# rapidshark-display-butt-mk-1_2.net
KiCad netlist of a schematic drawn in EAGLE
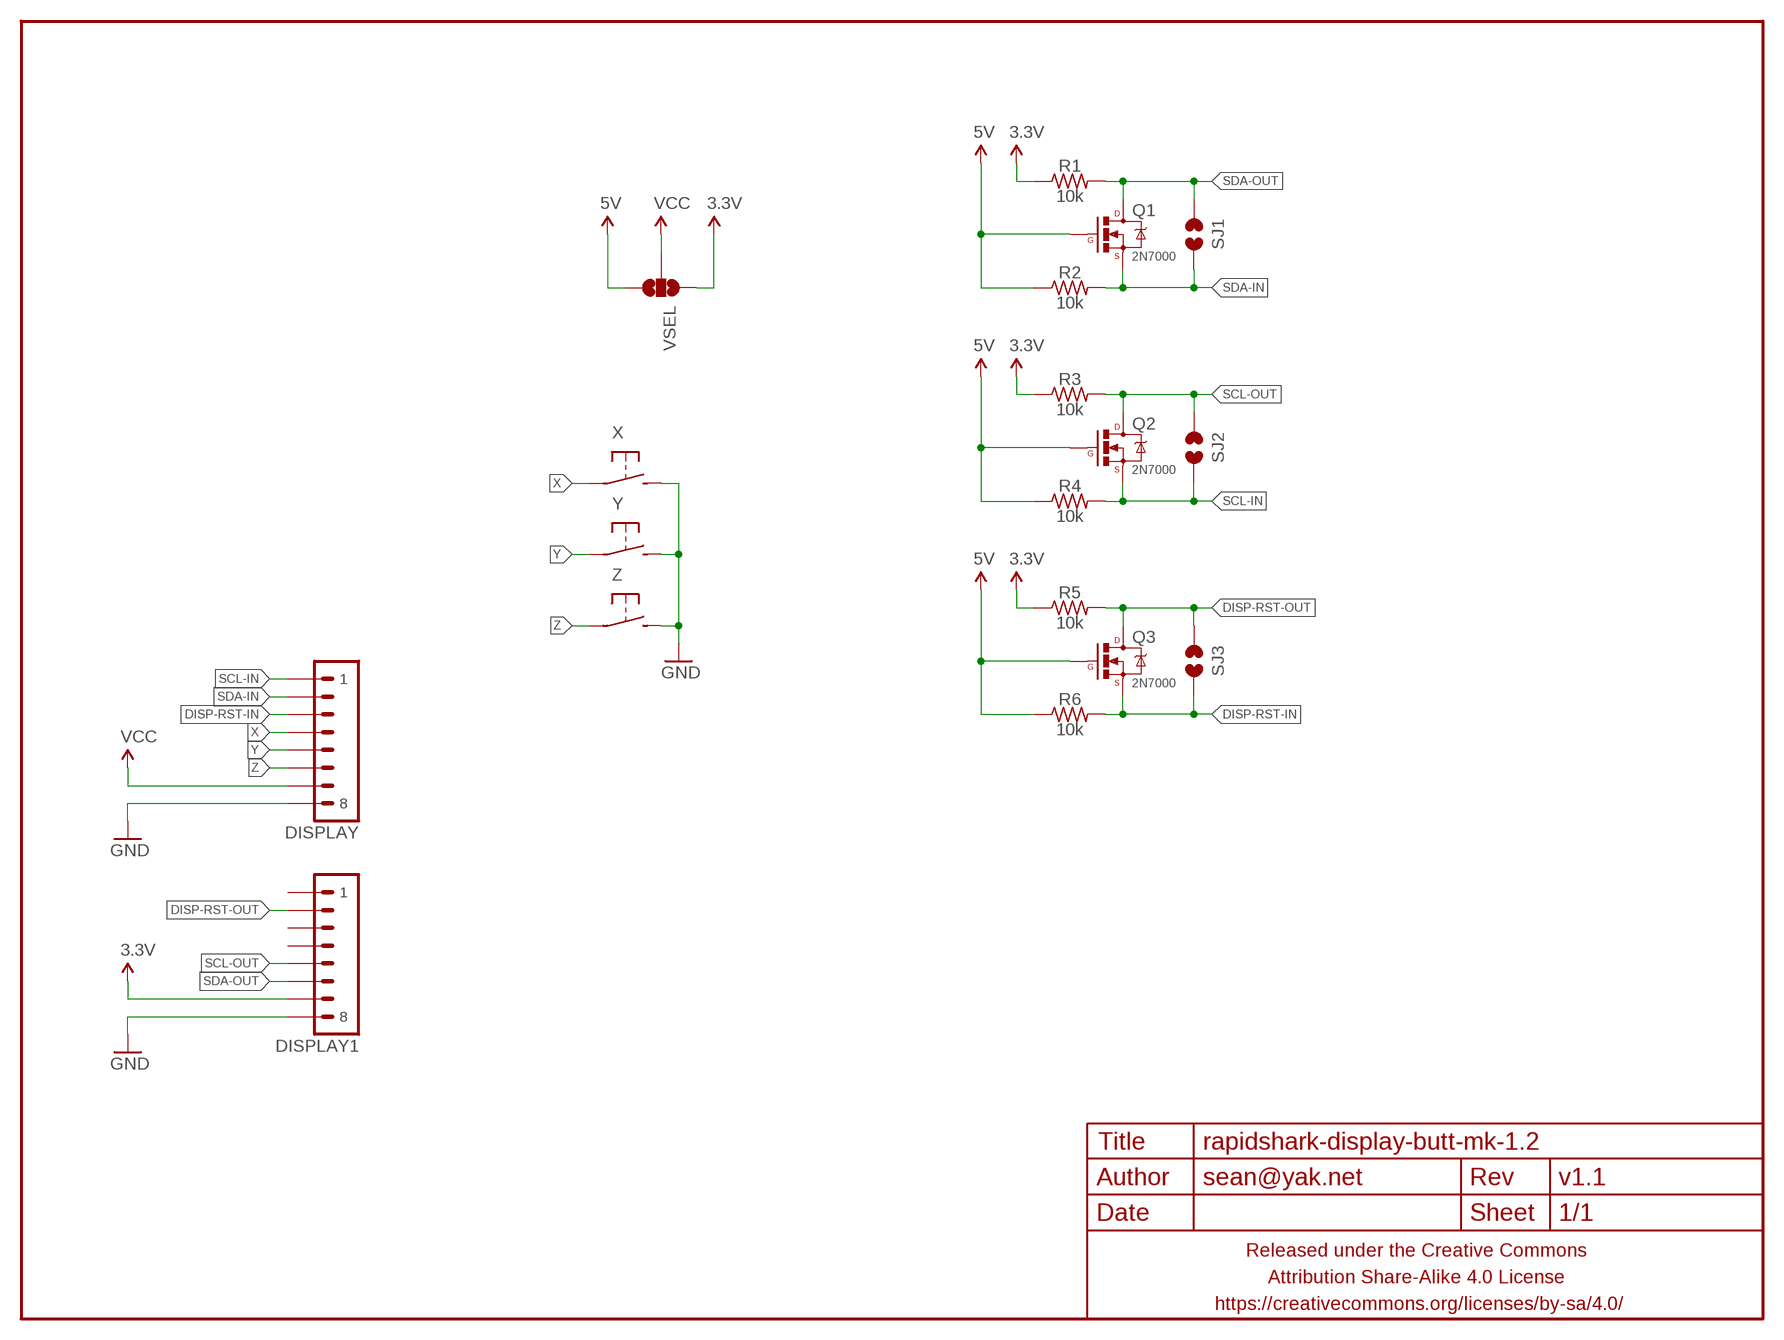
[diagram p0: schematic, sheet 1]

(export (version "E")
  (design (tool "Eeschema 10.0.6"))
  (components
    (comp (ref "DISPLAY")
      (value "M08JST-PH-VERT-PTH")
      (footprint "eagle-import:JST-8-VERT-PTH")
      (libsource (lib "eagle-import") (part "M08JST-PH-VERT-PTH"))
    )
    (comp (ref "DISPLAY1")
      (value "M081X08")
      (footprint "eagle-import:1X08")
      (libsource (lib "eagle-import") (part "M081X08"))
    )
    (comp (ref "FRAME1")
      (value "FRAME-LETTERNO_PACKAGE")
      (footprint "eagle-import:DUMMY")
      (fields (field (name "DESIGNER") "sean@yak.net") (field (name "VERSION") "v1.1"))
      (libsource (lib "eagle-import") (part "FRAME-LETTERNO_PACKAGE"))
    )
    (comp (ref "Q1")
      (value "2N7000")
      (footprint "eagle-import:TO-92-AMMO")
      (libsource (lib "eagle-import") (part "MOSFET-NCHANNEL2N7000-AMMO"))
    )
    (comp (ref "Q2")
      (value "2N7000")
      (footprint "eagle-import:TO-92-AMMO")
      (libsource (lib "eagle-import") (part "MOSFET-NCHANNEL2N7000-AMMO"))
    )
    (comp (ref "Q3")
      (value "2N7000")
      (footprint "eagle-import:TO-92-AMMO")
      (libsource (lib "eagle-import") (part "MOSFET-NCHANNEL2N7000-AMMO"))
    )
    (comp (ref "R1")
      (value "10k")
      (footprint "eagle-import:RESISTOR-AXIAL-PTH-5.08MM")
      (libsource (lib "eagle-import") (part "RESISTORPTH-AXIAL-5.08MM"))
    )
    (comp (ref "R2")
      (value "10k")
      (footprint "eagle-import:RESISTOR-AXIAL-PTH-5.08MM")
      (libsource (lib "eagle-import") (part "RESISTORPTH-AXIAL-5.08MM"))
    )
    (comp (ref "R3")
      (value "10k")
      (footprint "eagle-import:RESISTOR-AXIAL-PTH-5.08MM")
      (libsource (lib "eagle-import") (part "RESISTORPTH-AXIAL-5.08MM"))
    )
    (comp (ref "R4")
      (value "10k")
      (footprint "eagle-import:RESISTOR-AXIAL-PTH-5.08MM")
      (libsource (lib "eagle-import") (part "RESISTORPTH-AXIAL-5.08MM"))
    )
    (comp (ref "R5")
      (value "10k")
      (footprint "eagle-import:RESISTOR-AXIAL-PTH-5.08MM")
      (libsource (lib "eagle-import") (part "RESISTORPTH-AXIAL-5.08MM"))
    )
    (comp (ref "R6")
      (value "10k")
      (footprint "eagle-import:RESISTOR-AXIAL-PTH-5.08MM")
      (libsource (lib "eagle-import") (part "RESISTORPTH-AXIAL-5.08MM"))
    )
    (comp (ref "SJ1")
      (value "JUMPER-PAD-2-NOYES_SILK")
      (footprint "eagle-import:PAD-JUMPER-2-NO_YES_SILK")
      (libsource (lib "eagle-import") (part "JUMPER-PAD-2-NOYES_SILK"))
    )
    (comp (ref "SJ2")
      (value "JUMPER-PAD-2-NOYES_SILK")
      (footprint "eagle-import:PAD-JUMPER-2-NO_YES_SILK")
      (libsource (lib "eagle-import") (part "JUMPER-PAD-2-NOYES_SILK"))
    )
    (comp (ref "SJ3")
      (value "JUMPER-PAD-2-NOYES_SILK")
      (footprint "eagle-import:PAD-JUMPER-2-NO_YES_SILK")
      (libsource (lib "eagle-import") (part "JUMPER-PAD-2-NOYES_SILK"))
    )
    (comp (ref "VSEL")
      (value "JUMPER-PAD-3-NOFULL_BOX_SILK")
      (footprint "eagle-import:PAD-JUMPER-3-NO_YES_SILK_FULL_BOX")
      (libsource (lib "eagle-import") (part "JUMPER-PAD-3-NOFULL_BOX_SILK"))
    )
    (comp (ref "X")
      (value "SPST-NO-TACT6MM-PTH-SMALL-PADS")
      (footprint "eagle-import:DTS-6-SMALL-PADS")
      (libsource (lib "eagle-import") (part "SPST-NO-TACT6MM-PTH-SMALL-PADS"))
    )
    (comp (ref "Y")
      (value "SPST-NO-TACT6MM-PTH-SMALL-PADS")
      (footprint "eagle-import:DTS-6-SMALL-PADS")
      (libsource (lib "eagle-import") (part "SPST-NO-TACT6MM-PTH-SMALL-PADS"))
    )
    (comp (ref "Z")
      (value "SPST-NO-TACT6MM-PTH-SMALL-PADS")
      (footprint "eagle-import:DTS-6-SMALL-PADS")
      (libsource (lib "eagle-import") (part "SPST-NO-TACT6MM-PTH-SMALL-PADS"))
    )
  )
  (nets
    (net (code "1") (name "3.3V") (class "Default")
      (node (ref "DISPLAY1") (pin "7") (pinfunction "7_7") (pintype "passive"))
      (node (ref "R1") (pin "P$1") (pinfunction "1_P$1") (pintype "passive"))
      (node (ref "R3") (pin "P$1") (pinfunction "1_P$1") (pintype "passive"))
      (node (ref "R5") (pin "P$1") (pinfunction "1_P$1") (pintype "passive"))
      (node (ref "VSEL") (pin "1") (pinfunction "1_1") (pintype "passive"))
    )
    (net (code "2") (name "5V") (class "Default")
      (node (ref "Q1") (pin "2") (pinfunction "G_2") (pintype "passive"))
      (node (ref "Q2") (pin "2") (pinfunction "G_2") (pintype "passive"))
      (node (ref "Q3") (pin "2") (pinfunction "G_2") (pintype "passive"))
      (node (ref "R2") (pin "P$1") (pinfunction "1_P$1") (pintype "passive"))
      (node (ref "R4") (pin "P$1") (pinfunction "1_P$1") (pintype "passive"))
      (node (ref "R6") (pin "P$1") (pinfunction "1_P$1") (pintype "passive"))
      (node (ref "VSEL") (pin "3") (pinfunction "3_3") (pintype "passive"))
    )
    (net (code "3") (name "DISP-RST-IN") (class "Default")
      (node (ref "DISPLAY") (pin "3") (pinfunction "3_3") (pintype "passive"))
      (node (ref "Q3") (pin "1") (pinfunction "S_1") (pintype "passive"))
      (node (ref "R6") (pin "P$2") (pinfunction "2_P$2") (pintype "passive"))
      (node (ref "SJ3") (pin "1") (pinfunction "1_1") (pintype "passive"))
    )
    (net (code "4") (name "DISP-RST-OUT") (class "Default")
      (node (ref "DISPLAY1") (pin "2") (pinfunction "2_2") (pintype "passive"))
      (node (ref "Q3") (pin "3") (pinfunction "D_3") (pintype "passive"))
      (node (ref "R5") (pin "P$2") (pinfunction "2_P$2") (pintype "passive"))
      (node (ref "SJ3") (pin "2") (pinfunction "2_2") (pintype "passive"))
    )
    (net (code "5") (name "GND") (class "Default")
      (node (ref "DISPLAY") (pin "8") (pinfunction "8_8") (pintype "passive"))
      (node (ref "DISPLAY1") (pin "8") (pinfunction "8_8") (pintype "passive"))
      (node (ref "X") (pin "3") (pinfunction "2_3") (pintype "passive"))
      (node (ref "X") (pin "4") (pinfunction "2_4") (pintype "passive"))
      (node (ref "Y") (pin "3") (pinfunction "2_3") (pintype "passive"))
      (node (ref "Y") (pin "4") (pinfunction "2_4") (pintype "passive"))
      (node (ref "Z") (pin "3") (pinfunction "2_3") (pintype "passive"))
      (node (ref "Z") (pin "4") (pinfunction "2_4") (pintype "passive"))
    )
    (net (code "6") (name "SCL-IN") (class "Default")
      (node (ref "DISPLAY") (pin "1") (pinfunction "1_1") (pintype "passive"))
      (node (ref "Q2") (pin "1") (pinfunction "S_1") (pintype "passive"))
      (node (ref "R4") (pin "P$2") (pinfunction "2_P$2") (pintype "passive"))
      (node (ref "SJ2") (pin "1") (pinfunction "1_1") (pintype "passive"))
    )
    (net (code "7") (name "SCL-OUT") (class "Default")
      (node (ref "DISPLAY1") (pin "5") (pinfunction "5_5") (pintype "passive"))
      (node (ref "Q2") (pin "3") (pinfunction "D_3") (pintype "passive"))
      (node (ref "R3") (pin "P$2") (pinfunction "2_P$2") (pintype "passive"))
      (node (ref "SJ2") (pin "2") (pinfunction "2_2") (pintype "passive"))
    )
    (net (code "8") (name "SDA-IN") (class "Default")
      (node (ref "DISPLAY") (pin "2") (pinfunction "2_2") (pintype "passive"))
      (node (ref "Q1") (pin "1") (pinfunction "S_1") (pintype "passive"))
      (node (ref "R2") (pin "P$2") (pinfunction "2_P$2") (pintype "passive"))
      (node (ref "SJ1") (pin "1") (pinfunction "1_1") (pintype "passive"))
    )
    (net (code "9") (name "SDA-OUT") (class "Default")
      (node (ref "DISPLAY1") (pin "6") (pinfunction "6_6") (pintype "passive"))
      (node (ref "Q1") (pin "3") (pinfunction "D_3") (pintype "passive"))
      (node (ref "R1") (pin "P$2") (pinfunction "2_P$2") (pintype "passive"))
      (node (ref "SJ1") (pin "2") (pinfunction "2_2") (pintype "passive"))
    )
    (net (code "10") (name "VCC") (class "Default")
      (node (ref "DISPLAY") (pin "7") (pinfunction "7_7") (pintype "passive"))
      (node (ref "VSEL") (pin "2") (pinfunction "2_2") (pintype "passive"))
    )
    (net (code "11") (name "X") (class "Default")
      (node (ref "DISPLAY") (pin "4") (pinfunction "4_4") (pintype "passive"))
      (node (ref "X") (pin "1") (pinfunction "1_1") (pintype "passive"))
      (node (ref "X") (pin "2") (pinfunction "1_2") (pintype "passive"))
    )
    (net (code "12") (name "Y") (class "Default")
      (node (ref "DISPLAY") (pin "5") (pinfunction "5_5") (pintype "passive"))
      (node (ref "Y") (pin "1") (pinfunction "1_1") (pintype "passive"))
      (node (ref "Y") (pin "2") (pinfunction "1_2") (pintype "passive"))
    )
    (net (code "13") (name "Z") (class "Default")
      (node (ref "DISPLAY") (pin "6") (pinfunction "6_6") (pintype "passive"))
      (node (ref "Z") (pin "1") (pinfunction "1_1") (pintype "passive"))
      (node (ref "Z") (pin "2") (pinfunction "1_2") (pintype "passive"))
    )
    (net (code "14") (name "unconnected-(DISPLAY1-Pad1)") (class "Default")
      (node (ref "DISPLAY1") (pin "1") (pinfunction "1_1") (pintype "passive"))
    )
    (net (code "15") (name "unconnected-(DISPLAY1-Pad3)") (class "Default")
      (node (ref "DISPLAY1") (pin "3") (pinfunction "3_3") (pintype "passive"))
    )
    (net (code "16") (name "unconnected-(DISPLAY1-Pad4)") (class "Default")
      (node (ref "DISPLAY1") (pin "4") (pinfunction "4_4") (pintype "passive"))
    )
  )
)
